# Connectors.net
KiCad netlist of a schematic drawn in Altium Designer
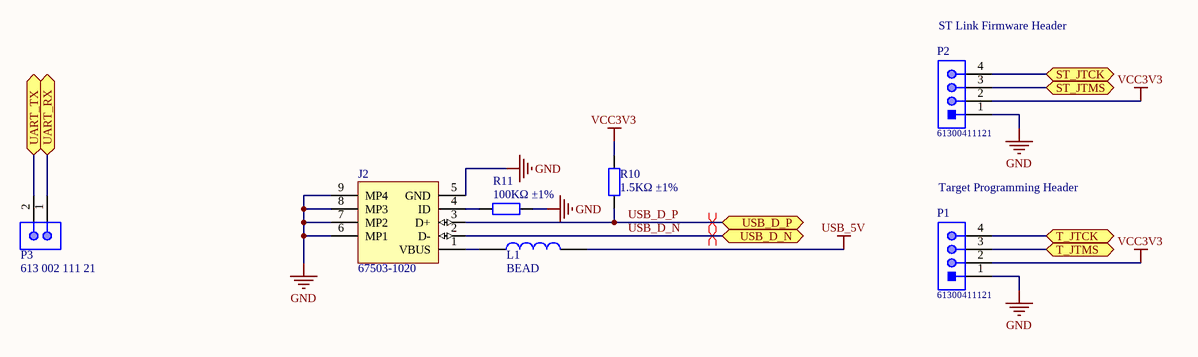
[diagram p0: Connectors.SchDoc]

(export (version "E")
  (design (tool "Eeschema 10.0.6"))
  (components
    (comp (ref "J2")
      (value "67503-1020")
      (footprint "MOLX-67503-1020_V")
      (description "USB, MINI, SMD, RA KME04-USBMU03A01")
      (fields (field (name "MANUFACTURER") "Molex"))
      (libsource (lib "Altium Content Vault") (part "MOLX-67503-1020"))
    )
    (comp (ref "L1")
      (value "BEAD")
      (footprint "0603_L")
      (description "Ferrite Bead")
      (libsource (lib "FBEAD") (part "0603 100R@100Mhz 1A"))
    )
    (comp (ref "P1")
      (value "61300411121")
      (footprint "61300411121")
      (description "THT Vertical Pin Header WR-PHD, Pitch 2.54 mm, Single Row, 4 pins")
      (fields (field (name "MANUFACTURER") "Wurth Elektronik") (field (name "PUBLISHER") "WurthElektronik"))
      (libsource (lib "Altium Content Vault") (part "WE-CN-1P-M-R4"))
    )
    (comp (ref "P2")
      (value "61300411121")
      (footprint "61300411121")
      (description "THT Vertical Pin Header WR-PHD, Pitch 2.54 mm, Single Row, 4 pins")
      (fields (field (name "MANUFACTURER") "Wurth Elektronik") (field (name "PUBLISHER") "WurthElektronik"))
      (libsource (lib "Altium Content Vault") (part "WE-CN-1P-M-R4"))
    )
    (comp (ref "P3")
      (value "613 002 111 21")
      (footprint "WE-61300211121_V")
      (libsource (lib "Altium Content Vault") (part "CN-1P-M-R2"))
    )
    (comp (ref "R10")
      (value "1.5KΩ ±1%")
      (footprint "0402_R")
      (description "Chip resistor")
      (fields (field (name "MANUFACTURER") "Uniroyal Elec") (field (name "PARTNUMBER") "0402WGF1501TCE"))
      (libsource (lib "Miscellaneous Devices LC") (part "0402 1.5K (1501) 1%"))
    )
    (comp (ref "R11")
      (value "100KΩ ±1%")
      (footprint "0402_R")
      (description "Chip resistor")
      (fields (field (name "MANUFACTURER") "Uniroyal Elec") (field (name "PARTNUMBER") "0402WGF1003TCE"))
      (libsource (lib "Miscellaneous Devices LC") (part "0402 100K (1003) 1%"))
    )
  )
  (nets
    (net (code "1") (name "/ST_JTCK") (class "Default")
      (node (ref "P2") (pin "4") (pinfunction "4_4") (pintype "passive"))
    )
    (net (code "2") (name "/ST_JTMS") (class "Default")
      (node (ref "P2") (pin "3") (pinfunction "3_3") (pintype "passive"))
    )
    (net (code "3") (name "/T_JTCK") (class "Default")
      (node (ref "P1") (pin "4") (pinfunction "4_4") (pintype "passive"))
    )
    (net (code "4") (name "/T_JTMS") (class "Default")
      (node (ref "P1") (pin "3") (pinfunction "3_3") (pintype "passive"))
    )
    (net (code "5") (name "/UART_RX") (class "Default")
      (node (ref "P3") (pin "1") (pinfunction "1_1") (pintype "passive"))
    )
    (net (code "6") (name "/UART_TX") (class "Default")
      (node (ref "P3") (pin "2") (pinfunction "2_2") (pintype "passive"))
    )
    (net (code "7") (name "/USB_D_N") (class "Default")
      (node (ref "J2") (pin "2") (pinfunction "D-_2") (pintype "bidirectional"))
    )
    (net (code "8") (name "/USB_D_P") (class "Default")
      (node (ref "J2") (pin "3") (pinfunction "D+_3") (pintype "bidirectional"))
      (node (ref "R10") (pin "1") (pinfunction "1_1") (pintype "passive"))
    )
    (net (code "9") (name "GND") (class "Default")
      (node (ref "J2") (pin "5") (pinfunction "GND_5") (pintype "power_in"))
      (node (ref "J2") (pin "6") (pinfunction "MP1_6") (pintype "passive"))
      (node (ref "J2") (pin "7") (pinfunction "MP2_7") (pintype "passive"))
      (node (ref "J2") (pin "8") (pinfunction "MP3_8") (pintype "passive"))
      (node (ref "J2") (pin "9") (pinfunction "MP4_9") (pintype "passive"))
      (node (ref "P1") (pin "1") (pinfunction "1_1") (pintype "passive"))
      (node (ref "P2") (pin "1") (pinfunction "1_1") (pintype "passive"))
      (node (ref "R11") (pin "2") (pinfunction "2_2") (pintype "passive"))
    )
    (net (code "10") (name "Net-(J2-ID)") (class "Default")
      (node (ref "J2") (pin "4") (pinfunction "ID_4") (pintype "passive"))
      (node (ref "R11") (pin "1") (pinfunction "1_1") (pintype "passive"))
    )
    (net (code "11") (name "Net-(J2-VBUS)") (class "Default")
      (node (ref "J2") (pin "1") (pinfunction "VBUS_1") (pintype "power_in"))
      (node (ref "L1") (pin "1") (pinfunction "1_1") (pintype "passive"))
    )
    (net (code "12") (name "USB_5V") (class "Default")
      (node (ref "L1") (pin "2") (pinfunction "2_2") (pintype "passive"))
    )
    (net (code "13") (name "VCC3V3") (class "Default")
      (node (ref "P1") (pin "2") (pinfunction "2_2") (pintype "passive"))
      (node (ref "P2") (pin "2") (pinfunction "2_2") (pintype "passive"))
      (node (ref "R10") (pin "2") (pinfunction "2_2") (pintype "passive"))
    )
  )
)
